# KEYBOARD_2020-05-21_13-30-03.net
KiCad netlist of a schematic drawn in Altium Designer
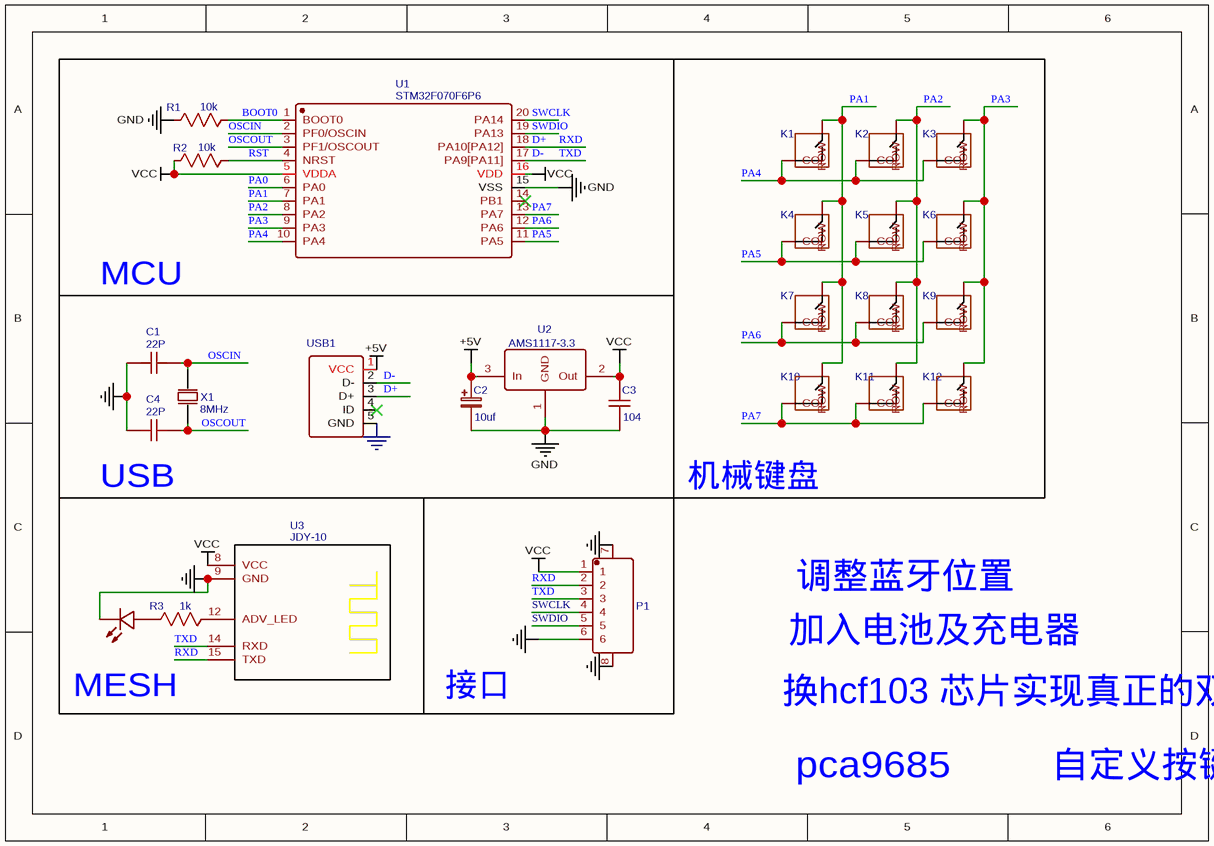
[diagram p0: KEYBOARD_2020-05-21_13-30-03.schdoc]

(export (version "E")
  (design (tool "Eeschema 10.0.6"))
  (components
    (comp (ref "C1") (value "22P") (libsource (lib "altium-import") (part "root_1_22P_")))
    (comp (ref "C2")
      (value "10uf")
      (fields (field (name "CONTRIBUTOR") "EasyEDA"))
      (libsource (lib "altium-import") (part "root_0_10uf_"))
    )
    (comp (ref "C3") (value "104") (libsource (lib "altium-import") (part "root_0_104_")))
    (comp (ref "C4") (value "22P") (libsource (lib "altium-import") (part "root_1_22P_")))
    (comp (ref "K1")
      (value "机械键盘轴")
      (fields (field (name "CONTRIBUTOR") "booooy"))
      (libsource (lib "altium-import") (part "root_0_机械键盘轴_"))
    )
    (comp (ref "K2")
      (value "机械键盘轴")
      (fields (field (name "CONTRIBUTOR") "booooy"))
      (libsource (lib "altium-import") (part "root_0_机械键盘轴_"))
    )
    (comp (ref "K3")
      (value "机械键盘轴")
      (fields (field (name "CONTRIBUTOR") "booooy"))
      (libsource (lib "altium-import") (part "root_0_机械键盘轴_"))
    )
    (comp (ref "K4")
      (value "机械键盘轴")
      (fields (field (name "CONTRIBUTOR") "booooy"))
      (libsource (lib "altium-import") (part "root_0_机械键盘轴_"))
    )
    (comp (ref "K5")
      (value "机械键盘轴")
      (fields (field (name "CONTRIBUTOR") "booooy"))
      (libsource (lib "altium-import") (part "root_0_机械键盘轴_"))
    )
    (comp (ref "K6")
      (value "机械键盘轴")
      (fields (field (name "CONTRIBUTOR") "booooy"))
      (libsource (lib "altium-import") (part "root_0_机械键盘轴_"))
    )
    (comp (ref "K7")
      (value "机械键盘轴")
      (fields (field (name "CONTRIBUTOR") "booooy"))
      (libsource (lib "altium-import") (part "root_0_机械键盘轴_"))
    )
    (comp (ref "K8")
      (value "机械键盘轴")
      (fields (field (name "CONTRIBUTOR") "booooy"))
      (libsource (lib "altium-import") (part "root_0_机械键盘轴_"))
    )
    (comp (ref "K9")
      (value "机械键盘轴")
      (fields (field (name "CONTRIBUTOR") "booooy"))
      (libsource (lib "altium-import") (part "root_0_机械键盘轴_"))
    )
    (comp (ref "K10")
      (value "机械键盘轴")
      (fields (field (name "CONTRIBUTOR") "booooy"))
      (libsource (lib "altium-import") (part "root_0_机械键盘轴_"))
    )
    (comp (ref "K11")
      (value "机械键盘轴")
      (fields (field (name "CONTRIBUTOR") "booooy"))
      (libsource (lib "altium-import") (part "root_0_机械键盘轴_"))
    )
    (comp (ref "K12")
      (value "机械键盘轴")
      (fields (field (name "CONTRIBUTOR") "booooy"))
      (libsource (lib "altium-import") (part "root_0_机械键盘轴_"))
    )
    (comp (ref "LED1")
      (value "204-10SURD/S530-A3")
      (fields (field (name "BOM_SUPPLIER PART") "C99772"))
      (libsource (lib "altium-import") (part "root_2_204-10SURD/S530-A3_"))
    )
    (comp (ref "P1")
      (value "FPC 0.5MM 6P Pull type H2.0mm Pick up")
      (fields (field (name "BOM_SUPPLIER PART") "C11083"))
      (libsource (lib "altium-import") (part "root_0_FPC 0.5MM 6P Pull type H2.0mm Pick up_"))
    )
    (comp (ref "R1") (value "10k") (libsource (lib "") (part "root_2_10k__1")))
    (comp (ref "R2") (value "10k") (libsource (lib "altium-import") (part "root_2_10k_")))
    (comp (ref "R3") (value "1k") (libsource (lib "altium-import") (part "root_2_1k_")))
    (comp (ref "U1")
      (value "STM32F070F6P6")
      (fields (field (name "BOM_SUPPLIER PART") "C86951"))
      (libsource (lib "altium-import") (part "root_0_STM32F070F6P6_"))
    )
    (comp (ref "U2")
      (value "AMS1117-3.3")
      (fields
        (field (name "BOM_MANUFACTURER PART") "AMS1117-5.0")
        (field (name "BOM_SUPPLIER PART") "C6187")
        (field (name "CONTRIBUTOR") "qianlihaoyue")
      )
      (libsource (lib "altium-import") (part "root_0_AMS1117-3.3_"))
    )
    (comp (ref "U3")
      (value "JDY-10")
      (fields (field (name "CONTRIBUTOR") "qianlihaoyue"))
      (libsource (lib "altium-import") (part "root_3_JDY-10_"))
    )
    (comp (ref "USB1")
      (value "Micro USB")
      (fields
        (field (name "BOM_MANUFACTURER PART") "Micro USB-B 5P_C40942")
        (field (name "BOM_SUPPLIER PART") "C40942")
      )
      (libsource (lib "altium-import") (part "root_0_Micro USB_"))
    )
    (comp (ref "X1")
      (value "8MHz")
      (fields
        (field (name "BOM_MANUFACTURER PART") "X503224MSB2GI")
        (field (name "BOM_SUPPLIER PART") "C112570")
      )
      (libsource (lib "altium-import") (part "root_1_8MHz_"))
    )
  )
  (nets
    (net (code "1") (name "+5V") (class "Default")
      (node (ref "C2") (pin "1") (pinfunction "1_1") (pintype "passive"))
      (node (ref "U2") (pin "3") (pinfunction "In_3") (pintype "passive"))
      (node (ref "USB1") (pin "1") (pinfunction "VCC_1") (pintype "passive"))
    )
    (net (code "2") (name "/BOOT0") (class "Default")
      (node (ref "R1") (pin "1") (pinfunction "1_1") (pintype "passive"))
      (node (ref "U1") (pin "1") (pinfunction "BOOT0_1") (pintype "passive"))
    )
    (net (code "3") (name "/D+") (class "Default")
      (node (ref "P1") (pin "2") (pinfunction "2_2") (pintype "passive"))
      (node (ref "U1") (pin "18") (pinfunction "PA10[PA12]_18") (pintype "passive"))
      (node (ref "U3") (pin "15") (pinfunction "TXD_15") (pintype "passive"))
      (node (ref "USB1") (pin "3") (pinfunction "D+_3") (pintype "passive"))
    )
    (net (code "4") (name "/D-") (class "Default")
      (node (ref "P1") (pin "3") (pinfunction "3_3") (pintype "passive"))
      (node (ref "U1") (pin "17") (pinfunction "PA9[PA11]_17") (pintype "passive"))
      (node (ref "U3") (pin "14") (pinfunction "RXD_14") (pintype "passive"))
      (node (ref "USB1") (pin "2") (pinfunction "D-_2") (pintype "passive"))
    )
    (net (code "5") (name "/OSCIN") (class "Default")
      (node (ref "C1") (pin "1") (pinfunction "1_1") (pintype "passive"))
      (node (ref "U1") (pin "2") (pinfunction "PF0/OSCIN_2") (pintype "passive"))
      (node (ref "X1") (pin "2") (pinfunction "OSC2_2") (pintype "passive"))
    )
    (net (code "6") (name "/OSCOUT") (class "Default")
      (node (ref "C4") (pin "1") (pinfunction "1_1") (pintype "passive"))
      (node (ref "U1") (pin "3") (pinfunction "PF1/OSCOUT_3") (pintype "passive"))
      (node (ref "X1") (pin "1") (pinfunction "OSC1_1") (pintype "passive"))
    )
    (net (code "7") (name "/PA0") (class "Default")
      (node (ref "U1") (pin "6") (pinfunction "PA0_6") (pintype "passive"))
    )
    (net (code "8") (name "/PA1") (class "Default")
      (node (ref "K1") (pin "ROW") (pinfunction "ROW_ROW") (pintype "passive"))
      (node (ref "K10") (pin "ROW") (pinfunction "ROW_ROW") (pintype "passive"))
      (node (ref "K4") (pin "ROW") (pinfunction "ROW_ROW") (pintype "passive"))
      (node (ref "K7") (pin "ROW") (pinfunction "ROW_ROW") (pintype "passive"))
      (node (ref "U1") (pin "7") (pinfunction "PA1_7") (pintype "passive"))
    )
    (net (code "9") (name "/PA2") (class "Default")
      (node (ref "K11") (pin "ROW") (pinfunction "ROW_ROW") (pintype "passive"))
      (node (ref "K2") (pin "ROW") (pinfunction "ROW_ROW") (pintype "passive"))
      (node (ref "K5") (pin "ROW") (pinfunction "ROW_ROW") (pintype "passive"))
      (node (ref "K8") (pin "ROW") (pinfunction "ROW_ROW") (pintype "passive"))
      (node (ref "U1") (pin "8") (pinfunction "PA2_8") (pintype "passive"))
    )
    (net (code "10") (name "/PA3") (class "Default")
      (node (ref "K12") (pin "ROW") (pinfunction "ROW_ROW") (pintype "passive"))
      (node (ref "K3") (pin "ROW") (pinfunction "ROW_ROW") (pintype "passive"))
      (node (ref "K6") (pin "ROW") (pinfunction "ROW_ROW") (pintype "passive"))
      (node (ref "K9") (pin "ROW") (pinfunction "ROW_ROW") (pintype "passive"))
      (node (ref "U1") (pin "9") (pinfunction "PA3_9") (pintype "passive"))
    )
    (net (code "11") (name "/PA4") (class "Default")
      (node (ref "K1") (pin "COL") (pinfunction "COL_COL") (pintype "passive"))
      (node (ref "K2") (pin "COL") (pinfunction "COL_COL") (pintype "passive"))
      (node (ref "K3") (pin "COL") (pinfunction "COL_COL") (pintype "passive"))
      (node (ref "U1") (pin "10") (pinfunction "PA4_10") (pintype "passive"))
    )
    (net (code "12") (name "/PA5") (class "Default")
      (node (ref "K4") (pin "COL") (pinfunction "COL_COL") (pintype "passive"))
      (node (ref "K5") (pin "COL") (pinfunction "COL_COL") (pintype "passive"))
      (node (ref "K6") (pin "COL") (pinfunction "COL_COL") (pintype "passive"))
      (node (ref "U1") (pin "11") (pinfunction "PA5_11") (pintype "passive"))
    )
    (net (code "13") (name "/PA6") (class "Default")
      (node (ref "K7") (pin "COL") (pinfunction "COL_COL") (pintype "passive"))
      (node (ref "K8") (pin "COL") (pinfunction "COL_COL") (pintype "passive"))
      (node (ref "K9") (pin "COL") (pinfunction "COL_COL") (pintype "passive"))
      (node (ref "U1") (pin "12") (pinfunction "PA6_12") (pintype "passive"))
    )
    (net (code "14") (name "/PA7") (class "Default")
      (node (ref "K10") (pin "COL") (pinfunction "COL_COL") (pintype "passive"))
      (node (ref "K11") (pin "COL") (pinfunction "COL_COL") (pintype "passive"))
      (node (ref "K12") (pin "COL") (pinfunction "COL_COL") (pintype "passive"))
      (node (ref "U1") (pin "13") (pinfunction "PA7_13") (pintype "passive"))
    )
    (net (code "15") (name "/RST") (class "Default")
      (node (ref "R2") (pin "1") (pinfunction "1_1") (pintype "passive"))
      (node (ref "U1") (pin "4") (pinfunction "NRST_4") (pintype "passive"))
    )
    (net (code "16") (name "/SWCLK") (class "Default")
      (node (ref "P1") (pin "4") (pinfunction "4_4") (pintype "passive"))
      (node (ref "U1") (pin "20") (pinfunction "PA14_20") (pintype "passive"))
    )
    (net (code "17") (name "/SWDIO") (class "Default")
      (node (ref "P1") (pin "5") (pinfunction "5_5") (pintype "passive"))
      (node (ref "U1") (pin "19") (pinfunction "PA13_19") (pintype "passive"))
    )
    (net (code "18") (name "GND") (class "Default")
      (node (ref "C1") (pin "2") (pinfunction "2_2") (pintype "passive"))
      (node (ref "C2") (pin "2") (pinfunction "2_2") (pintype "passive"))
      (node (ref "C3") (pin "1") (pinfunction "1_1") (pintype "passive"))
      (node (ref "C4") (pin "2") (pinfunction "2_2") (pintype "passive"))
      (node (ref "LED1") (pin "2") (pinfunction "K_2") (pintype "passive"))
      (node (ref "P1") (pin "6") (pinfunction "6_6") (pintype "passive"))
      (node (ref "P1") (pin "7") (pinfunction "7_7") (pintype "passive"))
      (node (ref "P1") (pin "8") (pinfunction "8_8") (pintype "passive"))
      (node (ref "R1") (pin "2") (pinfunction "2_2") (pintype "passive"))
      (node (ref "U1") (pin "15") (pinfunction "VSS_15") (pintype "passive"))
      (node (ref "U2") (pin "1") (pinfunction "GND_1") (pintype "passive"))
      (node (ref "U3") (pin "9") (pinfunction "GND_9") (pintype "passive"))
      (node (ref "USB1") (pin "5") (pinfunction "GND_5") (pintype "passive"))
    )
    (net (code "19") (name "Net-(LED1-A)") (class "Default")
      (node (ref "LED1") (pin "1") (pinfunction "A_1") (pintype "passive"))
      (node (ref "R3") (pin "2") (pinfunction "2_2") (pintype "passive"))
    )
    (net (code "20") (name "Net-(U3-ADV_LED)") (class "Default")
      (node (ref "R3") (pin "1") (pinfunction "1_1") (pintype "passive"))
      (node (ref "U3") (pin "12") (pinfunction "ADV_LED_12") (pintype "passive"))
    )
    (net (code "21") (name "VCC") (class "Default")
      (node (ref "C3") (pin "2") (pinfunction "2_2") (pintype "passive"))
      (node (ref "P1") (pin "1") (pinfunction "1_1") (pintype "passive"))
      (node (ref "R2") (pin "2") (pinfunction "2_2") (pintype "passive"))
      (node (ref "U1") (pin "16") (pinfunction "VDD_16") (pintype "passive"))
      (node (ref "U1") (pin "5") (pinfunction "VDDA_5") (pintype "passive"))
      (node (ref "U2") (pin "2") (pinfunction "Out_2") (pintype "passive"))
      (node (ref "U3") (pin "8") (pinfunction "VCC_8") (pintype "passive"))
    )
    (net (code "22") (name "unconnected-(U1-PB1-Pad14)") (class "Default")
      (node (ref "U1") (pin "14") (pinfunction "PB1_14") (pintype "passive+no_connect"))
    )
    (net (code "23") (name "unconnected-(USB1-ID-Pad4)") (class "Default")
      (node (ref "USB1") (pin "4") (pinfunction "ID_4") (pintype "passive+no_connect"))
    )
  )
)
